# Assignment1-5VAC-DCReg.net
KiCad netlist of a schematic drawn in EAGLE
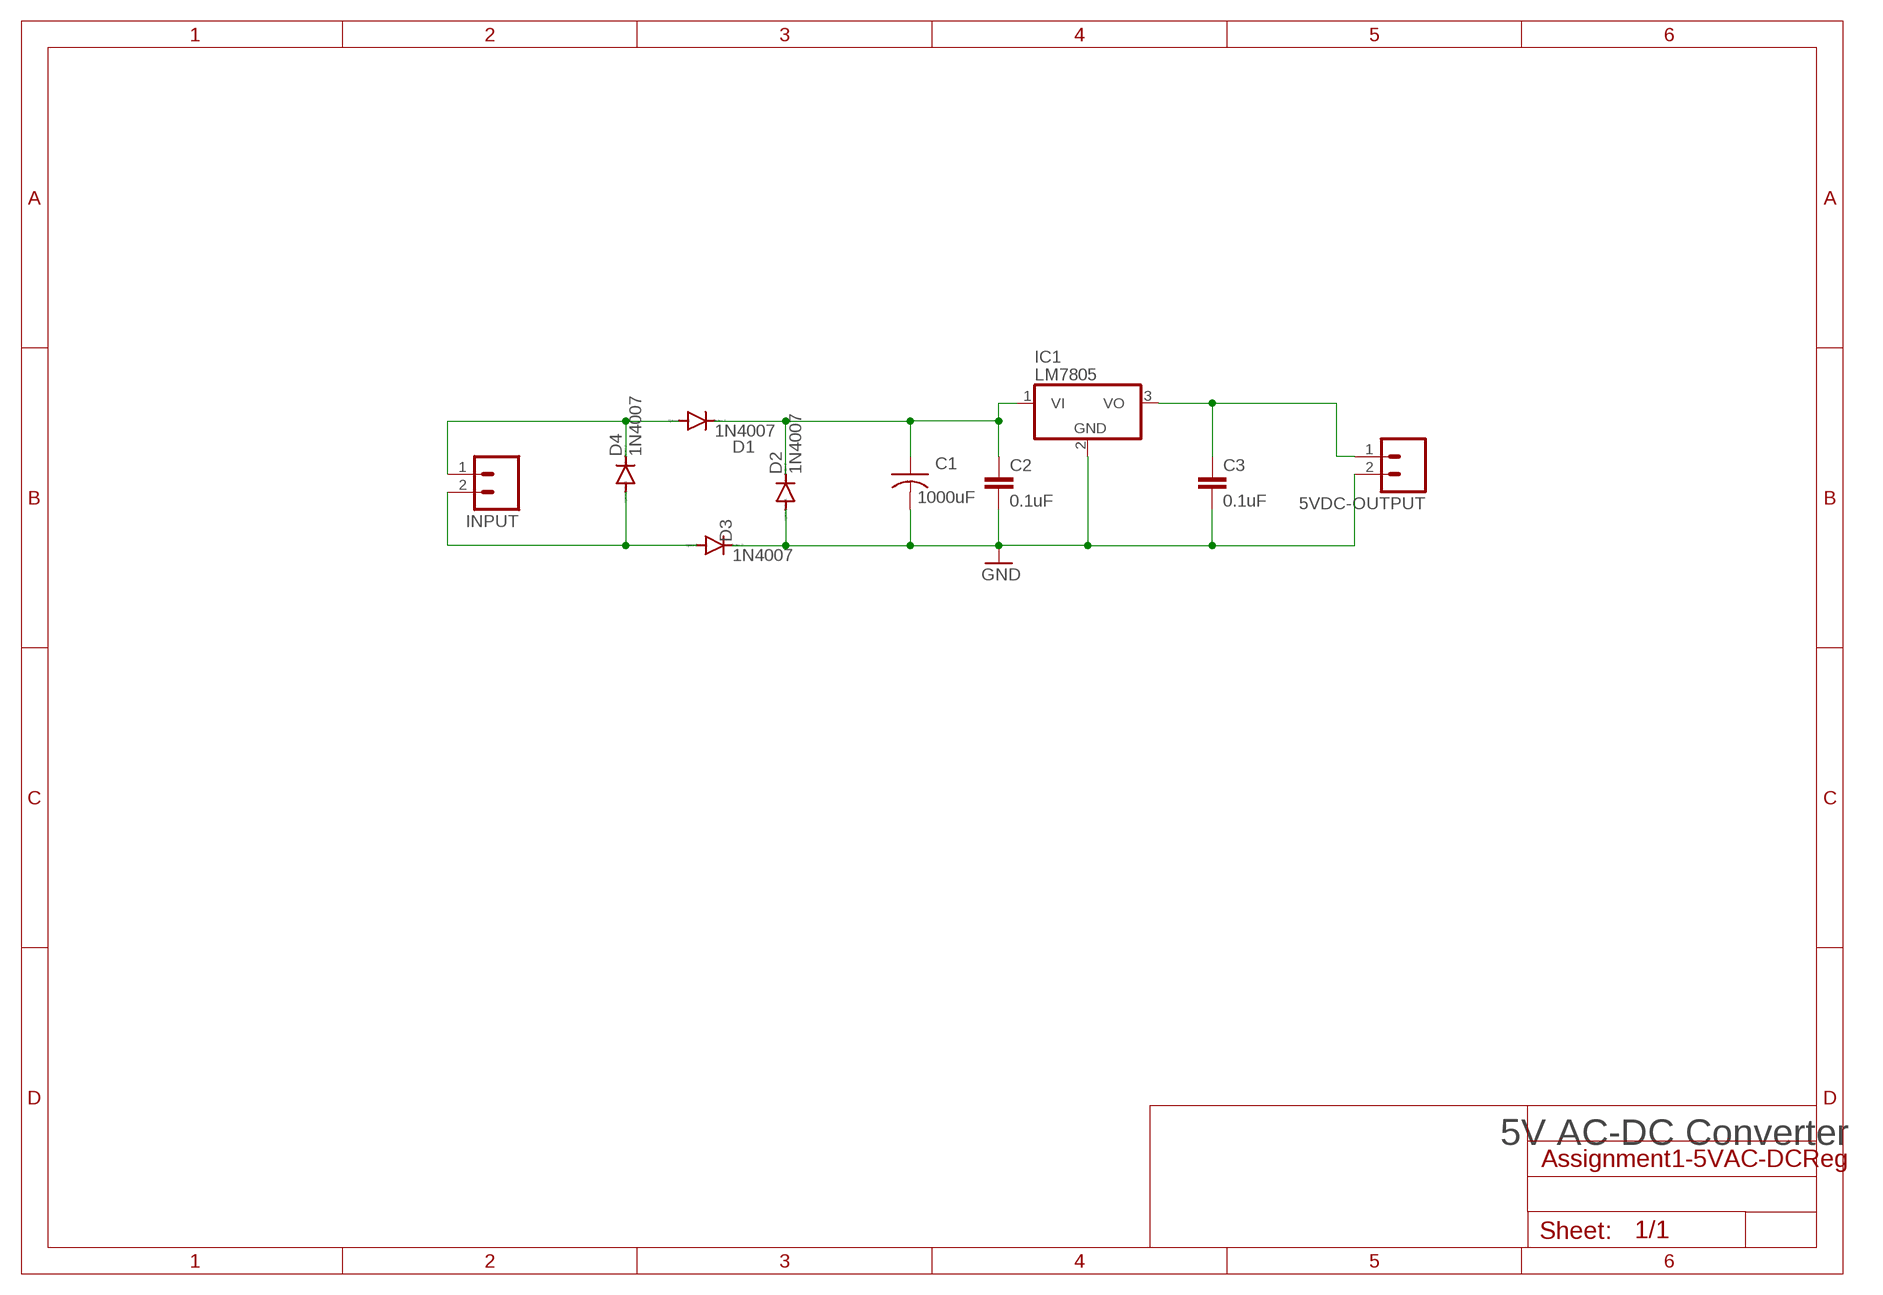
[diagram p0: schematic, sheet 1]

(export (version "E")
  (design (tool "Eeschema 10.0.6"))
  (components
    (comp (ref "5VDC-OUTPUT")
      (value "M02")
      (footprint "eagle-import:02P")
      (libsource (lib "eagle-import") (part "M02"))
    )
    (comp (ref "C1")
      (value "1000uF")
      (footprint "eagle-import:C025-024X044")
      (libsource (lib "eagle-import") (part "C-US025-024X044"))
    )
    (comp (ref "C2")
      (value "0.1uF")
      (footprint "eagle-import:C025-025X050")
      (libsource (lib "eagle-import") (part "C-EU025-025X050"))
    )
    (comp (ref "C3")
      (value "0.1uF")
      (footprint "eagle-import:C025-025X050")
      (libsource (lib "eagle-import") (part "C-EU025-025X050"))
    )
    (comp (ref "D1")
      (value "1N4007")
      (footprint "eagle-import:DO41-10")
      (libsource (lib "eagle-import") (part "1N4004"))
    )
    (comp (ref "D2")
      (value "1N4007")
      (footprint "eagle-import:DO41-10")
      (libsource (lib "eagle-import") (part "1N4004"))
    )
    (comp (ref "D3")
      (value "1N4007")
      (footprint "eagle-import:DO41-10")
      (libsource (lib "eagle-import") (part "1N4004"))
    )
    (comp (ref "D4")
      (value "1N4007")
      (footprint "eagle-import:DO41-10")
      (libsource (lib "eagle-import") (part "1N4004"))
    )
    (comp (ref "IC1")
      (value "LM7805")
      (footprint "eagle-import:TO220V")
      (libsource (lib "eagle-import") (part "78TV6"))
    )
    (comp (ref "INPUT")
      (value "M02")
      (footprint "eagle-import:02P")
      (libsource (lib "eagle-import") (part "M02"))
    )
  )
  (nets
    (net (code "1") (name "GND") (class "Default")
      (node (ref "5VDC-OUTPUT") (pin "2") (pinfunction "2_2") (pintype "passive"))
      (node (ref "C1") (pin "2") (pinfunction "2_2") (pintype "passive"))
      (node (ref "C2") (pin "2") (pinfunction "2_2") (pintype "passive"))
      (node (ref "C3") (pin "2") (pinfunction "2_2") (pintype "passive"))
      (node (ref "D2") (pin "A") (pinfunction "A_A") (pintype "passive"))
      (node (ref "D3") (pin "C") (pinfunction "C_C") (pintype "passive"))
      (node (ref "IC1") (pin "2") (pinfunction "GND_2") (pintype "passive"))
    )
    (net (code "2") (name "Net-(D1-PadA)") (class "Default")
      (node (ref "D1") (pin "A") (pinfunction "A_A") (pintype "passive"))
      (node (ref "D4") (pin "C") (pinfunction "C_C") (pintype "passive"))
      (node (ref "INPUT") (pin "1") (pinfunction "1_1") (pintype "passive"))
    )
    (net (code "3") (name "Net-(D3-PadA)") (class "Default")
      (node (ref "D3") (pin "A") (pinfunction "A_A") (pintype "passive"))
      (node (ref "D4") (pin "A") (pinfunction "A_A") (pintype "passive"))
      (node (ref "INPUT") (pin "2") (pinfunction "2_2") (pintype "passive"))
    )
    (net (code "4") (name "Net-(IC1-VI)") (class "Default")
      (node (ref "C1") (pin "1") (pinfunction "1_1") (pintype "passive"))
      (node (ref "C2") (pin "1") (pinfunction "1_1") (pintype "passive"))
      (node (ref "D1") (pin "C") (pinfunction "C_C") (pintype "passive"))
      (node (ref "D2") (pin "C") (pinfunction "C_C") (pintype "passive"))
      (node (ref "IC1") (pin "1") (pinfunction "VI_1") (pintype "input"))
    )
    (net (code "5") (name "Net-(IC1-VO)") (class "Default")
      (node (ref "5VDC-OUTPUT") (pin "1") (pinfunction "1_1") (pintype "passive"))
      (node (ref "C3") (pin "1") (pinfunction "1_1") (pintype "passive"))
      (node (ref "IC1") (pin "3") (pinfunction "VO_3") (pintype "passive"))
    )
  )
)
